# Actuators.net
KiCad netlist of a schematic drawn in Altium Designer
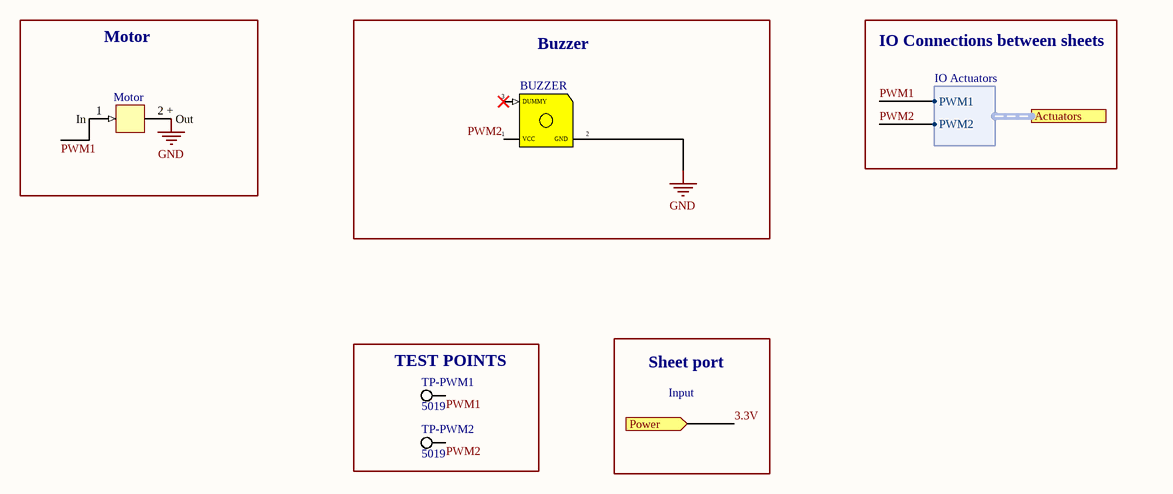
[diagram p0: Actuators.SchDoc]

(export (version "E")
  (design (tool "Eeschema 10.0.6"))
  (components
    (comp (ref "BUZZER")
      (value "Surface_Mount_Buzzer")
      (footprint "buzzer")
      (libsource (lib "FEEL2324") (part "Surface_Mount_Buzzer"))
    )
    (comp (ref "IN") (value "MOTOR") (footprint "Motor") (libsource (lib "FEEL2324") (part "MOTOR")))
    (comp (ref "TP-PWM1")
      (value "5019")
      (footprint "KSTN-5019_V")
      (description "Test Point, 1 Position SMD, RoHS, Tape and Reel")
      (libsource (lib "Altium Content Vault") (part "TESTPOINT_WHITE"))
    )
    (comp (ref "TP-PWM2")
      (value "5019")
      (footprint "KSTN-5019_V")
      (description "Test Point, 1 Position SMD, RoHS, Tape and Reel")
      (libsource (lib "Altium Content Vault") (part "TESTPOINT_WHITE"))
    )
  )
  (nets
    (net (code "4") (name "/PWM1") (class "Default")
      (node (ref "IN") (pin "1") (pinfunction "In_1") (pintype "input"))
      (node (ref "TP-PWM1") (pin "1") (pinfunction "1_1") (pintype "passive"))
    )
    (net (code "5") (name "/PWM2") (class "Default")
      (node (ref "BUZZER") (pin "1") (pinfunction "VCC_1") (pintype "passive"))
      (node (ref "TP-PWM2") (pin "1") (pinfunction "1_1") (pintype "passive"))
    )
    (net (code "7") (name "GND") (class "Default")
      (node (ref "BUZZER") (pin "2") (pinfunction "GND_2") (pintype "power_in"))
      (node (ref "IN") (pin "2_+") (pinfunction "Out_2_+") (pintype "power_in"))
    )
    (net (code "8") (name "unconnected-(BUZZER-DUMMY-Pad3)") (class "Default")
      (node (ref "BUZZER") (pin "3") (pinfunction "DUMMY_3") (pintype "input+no_connect"))
    )
  )
)
